# interfacing_board.net
KiCad netlist of a schematic drawn in EAGLE
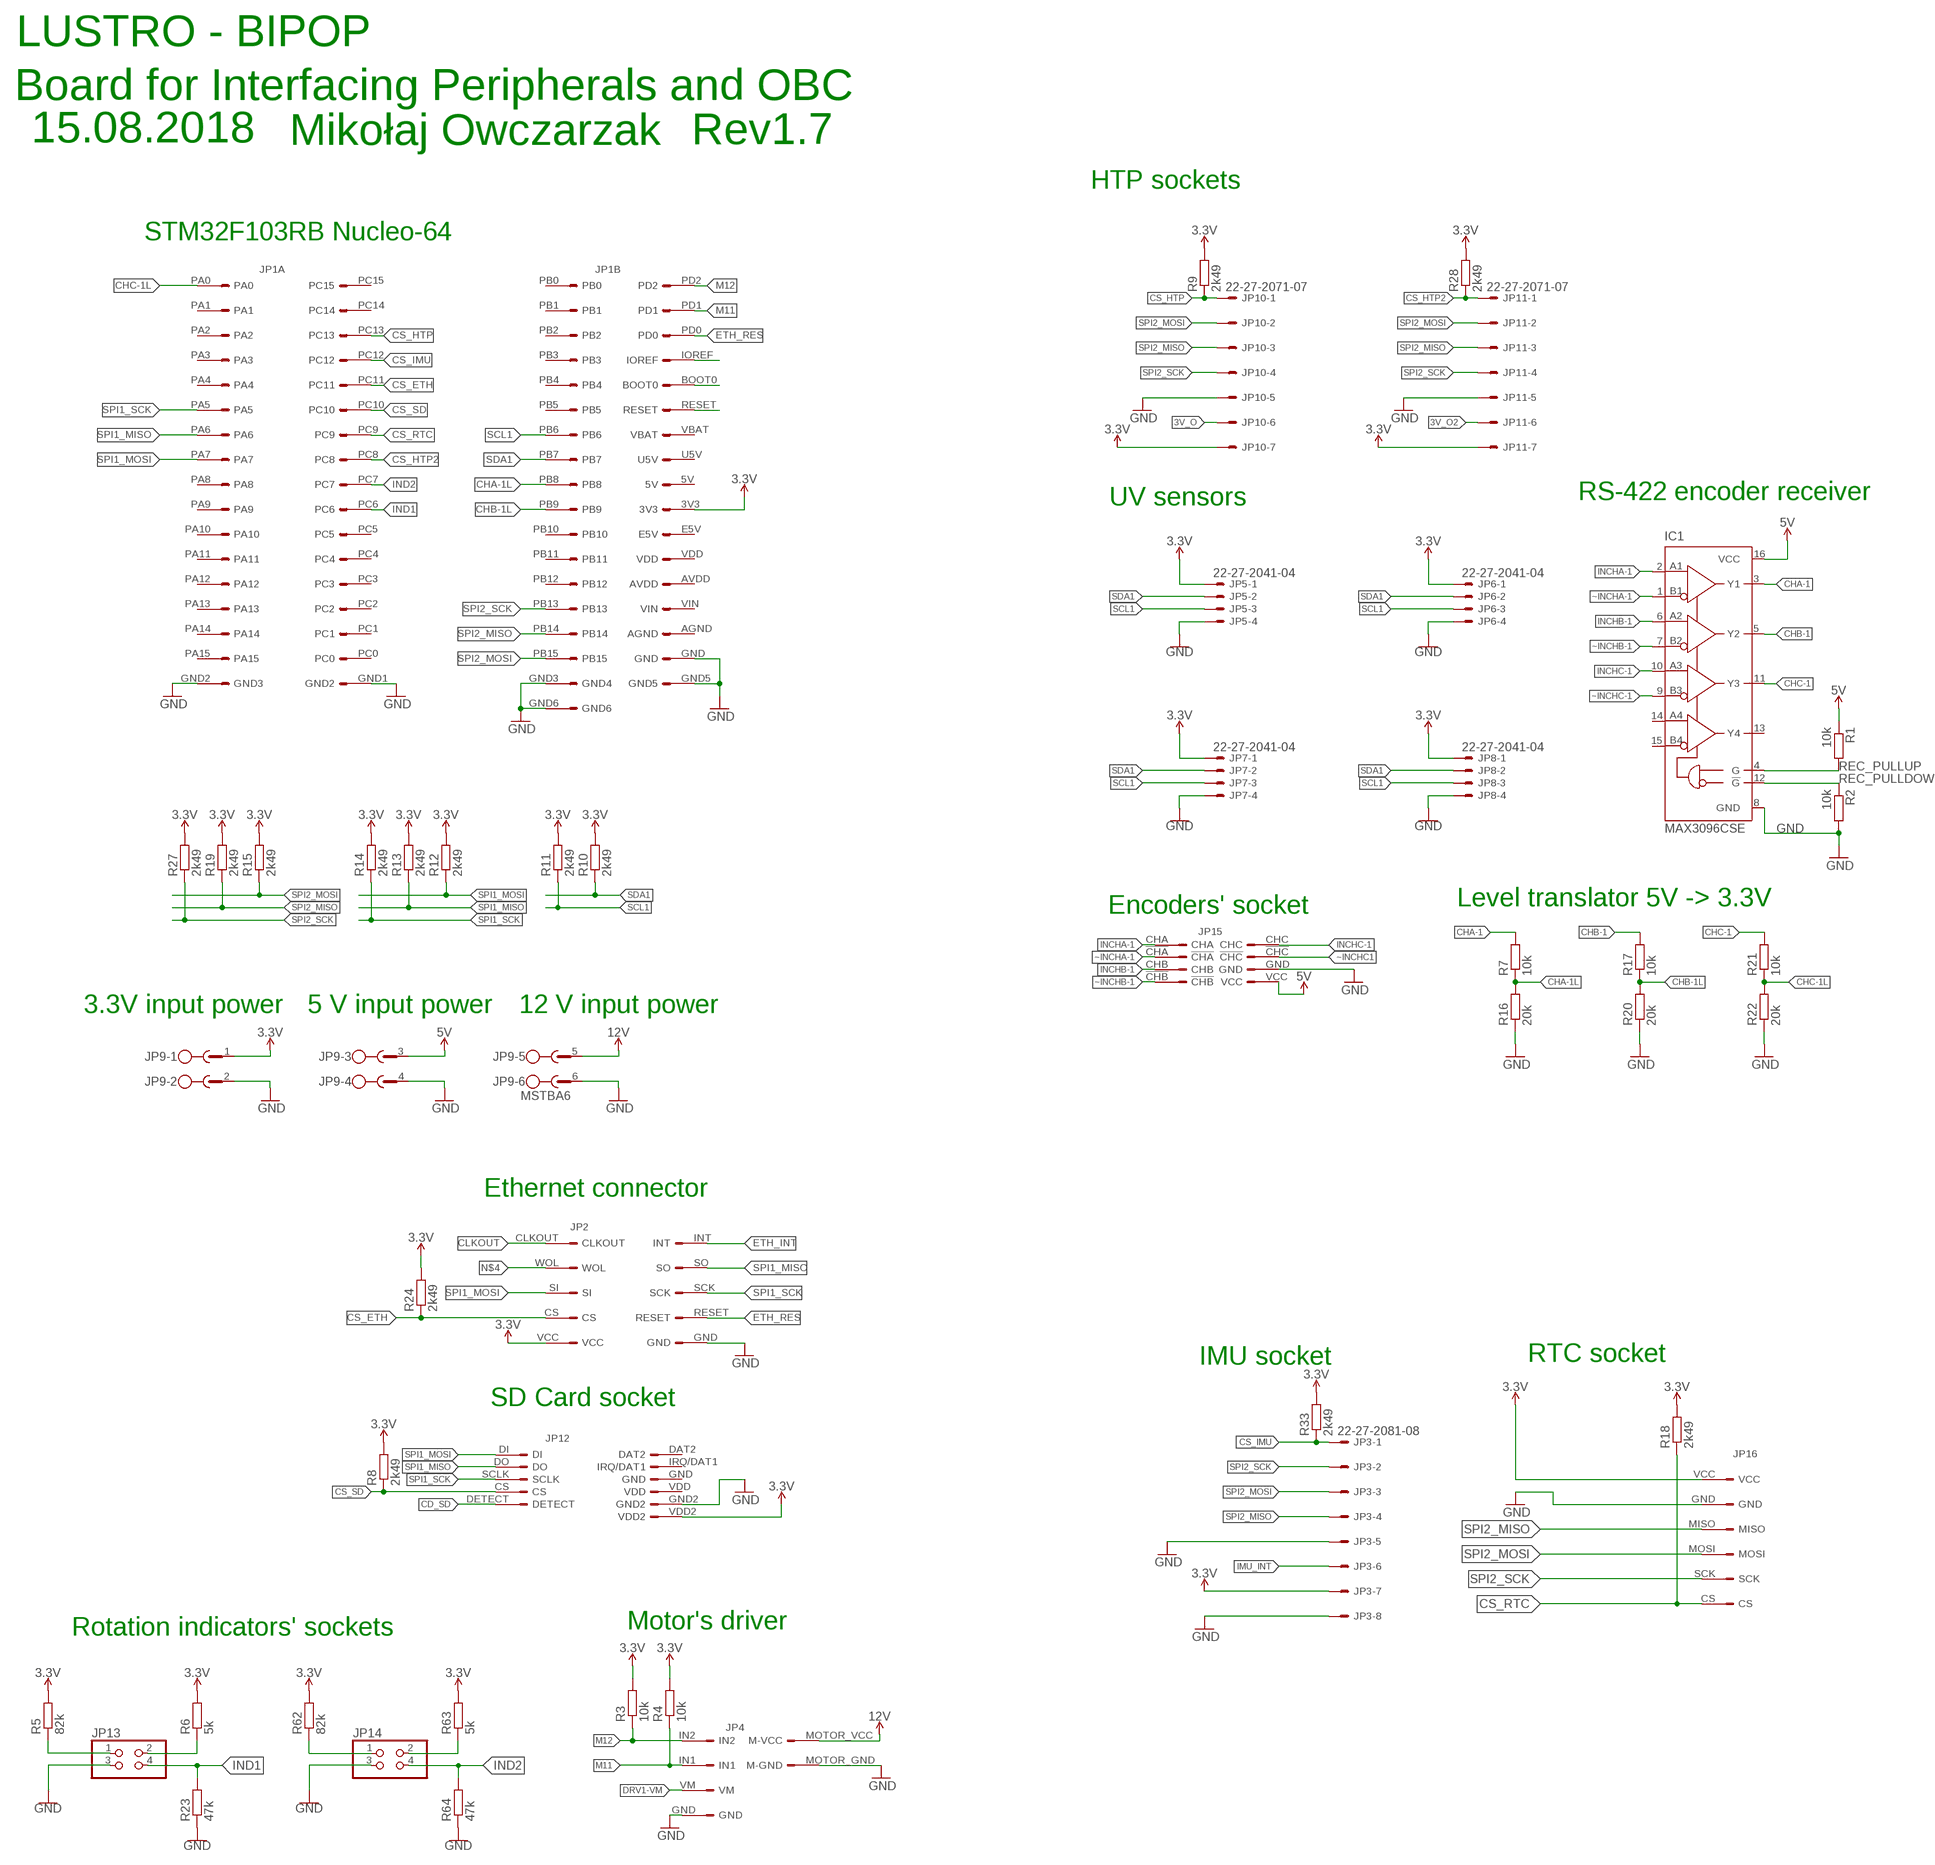
[diagram p0: schematic, sheet 1]

(export (version "E")
  (design (tool "Eeschema 10.0.6"))
  (components
    (comp (ref "IC1")
      (value "MAX3096CSE")
      (footprint "eagle-import:SO16")
      (fields (field (name "MF") "MAXIM") (field (name "MPN") "MAX3096CSE+"))
      (libsource (lib "eagle-import") (part "MAX309SE6C"))
    )
    (comp (ref "JP1A")
      (value "JP1B")
      (footprint "eagle-import:NUCLEO")
      (libsource (lib "eagle-import") (part "NUCLEOF103"))
    )
    (comp (ref "JP2")
      (value "ETHERNET")
      (footprint "eagle-import:ETHERNET")
      (libsource (lib "eagle-import") (part "ETHERNET"))
    )
    (comp (ref "JP3")
      (value "22-27-2081-08")
      (footprint "eagle-import:6410-08")
      (libsource (lib "eagle-import") (part "22-?-0827-2081"))
    )
    (comp (ref "JP4")
      (value "DRV8871")
      (footprint "eagle-import:DRIVER")
      (libsource (lib "eagle-import") (part "DRV8871"))
    )
    (comp (ref "JP5")
      (value "22-27-2041-04")
      (footprint "eagle-import:6410-04")
      (libsource (lib "eagle-import") (part "22-?-0427-2041"))
    )
    (comp (ref "JP6")
      (value "22-27-2041-04")
      (footprint "eagle-import:6410-04")
      (libsource (lib "eagle-import") (part "22-?-0427-2041"))
    )
    (comp (ref "JP7")
      (value "22-27-2041-04")
      (footprint "eagle-import:6410-04")
      (libsource (lib "eagle-import") (part "22-?-0427-2041"))
    )
    (comp (ref "JP8")
      (value "22-27-2041-04")
      (footprint "eagle-import:6410-04")
      (libsource (lib "eagle-import") (part "22-?-0427-2041"))
    )
    (comp (ref "JP9")
      (value "MSTBA6")
      (footprint "eagle-import:MSTBA6")
      (fields (field (name "MF") "FARNELL") (field (name "MPN") "1757284"))
      (libsource (lib "eagle-import") (part "MSTBA6"))
    )
    (comp (ref "JP10")
      (value "22-27-2071-07")
      (footprint "eagle-import:6410-07")
      (libsource (lib "eagle-import") (part "22-?-0727-2071"))
    )
    (comp (ref "JP11")
      (value "22-27-2071-07")
      (footprint "eagle-import:6410-07")
      (libsource (lib "eagle-import") (part "22-?-0727-2071"))
    )
    (comp (ref "JP12")
      (value "SD_2597")
      (footprint "eagle-import:SD")
      (libsource (lib "eagle-import") (part "SD_2597"))
    )
    (comp (ref "JP13")
      (value "PINHD-2X2")
      (footprint "eagle-import:2X02")
      (libsource (lib "eagle-import") (part "PINHD-2X2"))
    )
    (comp (ref "JP14")
      (value "PINHD-2X2")
      (footprint "eagle-import:2X02")
      (libsource (lib "eagle-import") (part "PINHD-2X2"))
    )
    (comp (ref "JP15")
      (value "ENX10")
      (footprint "eagle-import:SIL25")
      (libsource (lib "eagle-import") (part "ENX10"))
    )
    (comp (ref "JP16")
      (value "RTC_WAVESHARE")
      (footprint "eagle-import:RTC")
      (libsource (lib "eagle-import") (part "RTC_WAVESHARE"))
    )
    (comp (ref "R1")
      (value "10k")
      (footprint "eagle-import:M0805")
      (libsource (lib "eagle-import") (part "R-EU_M0805"))
    )
    (comp (ref "R2")
      (value "10k")
      (footprint "eagle-import:M0805")
      (libsource (lib "eagle-import") (part "R-EU_M0805"))
    )
    (comp (ref "R3")
      (value "10k")
      (footprint "eagle-import:M0805")
      (libsource (lib "eagle-import") (part "R-EU_M0805"))
    )
    (comp (ref "R4")
      (value "10k")
      (footprint "eagle-import:M0805")
      (libsource (lib "eagle-import") (part "R-EU_M0805"))
    )
    (comp (ref "R5")
      (value "82k")
      (footprint "eagle-import:M0805")
      (libsource (lib "eagle-import") (part "resistor_348_R-EU_M0805"))
    )
    (comp (ref "R6")
      (value "5k")
      (footprint "eagle-import:M0805")
      (libsource (lib "eagle-import") (part "resistor_348_R-EU_M0805"))
    )
    (comp (ref "R7")
      (value "10k")
      (footprint "eagle-import:M0805")
      (libsource (lib "eagle-import") (part "R-EU_M0805"))
    )
    (comp (ref "R8")
      (value "2k49")
      (footprint "eagle-import:M0805")
      (libsource (lib "eagle-import") (part "resistor_348_R-EU_M0805"))
    )
    (comp (ref "R9")
      (value "2k49")
      (footprint "eagle-import:M0805")
      (libsource (lib "eagle-import") (part "R-EU_M0805"))
    )
    (comp (ref "R10")
      (value "2k49")
      (footprint "eagle-import:M0805")
      (libsource (lib "eagle-import") (part "R-EU_M0805"))
    )
    (comp (ref "R11")
      (value "2k49")
      (footprint "eagle-import:M0805")
      (libsource (lib "eagle-import") (part "R-EU_M0805"))
    )
    (comp (ref "R12")
      (value "2k49")
      (footprint "eagle-import:M0805")
      (libsource (lib "eagle-import") (part "R-EU_M0805"))
    )
    (comp (ref "R13")
      (value "2k49")
      (footprint "eagle-import:M0805")
      (libsource (lib "eagle-import") (part "R-EU_M0805"))
    )
    (comp (ref "R14")
      (value "2k49")
      (footprint "eagle-import:M0805")
      (libsource (lib "eagle-import") (part "R-EU_M0805"))
    )
    (comp (ref "R15")
      (value "2k49")
      (footprint "eagle-import:M0805")
      (libsource (lib "eagle-import") (part "R-EU_M0805"))
    )
    (comp (ref "R16")
      (value "20k")
      (footprint "eagle-import:M0805")
      (libsource (lib "eagle-import") (part "R-EU_M0805"))
    )
    (comp (ref "R17")
      (value "10k")
      (footprint "eagle-import:M0805")
      (libsource (lib "eagle-import") (part "R-EU_M0805"))
    )
    (comp (ref "R18")
      (value "2k49")
      (footprint "eagle-import:R0805")
      (libsource (lib "eagle-import") (part "R-EU_R0805"))
    )
    (comp (ref "R19")
      (value "2k49")
      (footprint "eagle-import:M0805")
      (libsource (lib "eagle-import") (part "R-EU_M0805"))
    )
    (comp (ref "R20")
      (value "20k")
      (footprint "eagle-import:M0805")
      (libsource (lib "eagle-import") (part "R-EU_M0805"))
    )
    (comp (ref "R21")
      (value "10k")
      (footprint "eagle-import:M0805")
      (libsource (lib "eagle-import") (part "R-EU_M0805"))
    )
    (comp (ref "R22")
      (value "20k")
      (footprint "eagle-import:M0805")
      (libsource (lib "eagle-import") (part "R-EU_M0805"))
    )
    (comp (ref "R23")
      (value "47k")
      (footprint "eagle-import:M0805")
      (libsource (lib "eagle-import") (part "resistor_348_R-EU_M0805"))
    )
    (comp (ref "R24")
      (value "2k49")
      (footprint "eagle-import:M0805")
      (libsource (lib "eagle-import") (part "resistor_348_R-EU_M0805"))
    )
    (comp (ref "R27")
      (value "2k49")
      (footprint "eagle-import:M0805")
      (libsource (lib "eagle-import") (part "R-EU_M0805"))
    )
    (comp (ref "R28")
      (value "2k49")
      (footprint "eagle-import:M0805")
      (libsource (lib "eagle-import") (part "R-EU_M0805"))
    )
    (comp (ref "R33")
      (value "2k49")
      (footprint "eagle-import:M0805")
      (libsource (lib "eagle-import") (part "R-EU_M0805"))
    )
    (comp (ref "R62")
      (value "82k")
      (footprint "eagle-import:M0805")
      (libsource (lib "eagle-import") (part "resistor_348_R-EU_M0805"))
    )
    (comp (ref "R63")
      (value "5k")
      (footprint "eagle-import:M0805")
      (libsource (lib "eagle-import") (part "resistor_348_R-EU_M0805"))
    )
    (comp (ref "R64")
      (value "47k")
      (footprint "eagle-import:M0805")
      (libsource (lib "eagle-import") (part "resistor_348_R-EU_M0805"))
    )
  )
  (nets
    (net (code "1") (name "/REC_PULLDOWN") (class "Default")
      (node (ref "IC1") (pin "12") (pinfunction "~{G}_12") (pintype "input"))
      (node (ref "R2") (pin "1") (pinfunction "1_1") (pintype "passive"))
    )
    (net (code "2") (name "/REC_PULLUP") (class "Default")
      (node (ref "IC1") (pin "4") (pinfunction "G_4") (pintype "input"))
      (node (ref "R1") (pin "2") (pinfunction "2_2") (pintype "passive"))
    )
    (net (code "3") (name "/~{INCHA-1}") (class "Default")
      (node (ref "IC1") (pin "1") (pinfunction "B1_1") (pintype "output"))
      (node (ref "JP15") (pin "!CHA") (pinfunction "~{CHA}_!CHA") (pintype "bidirectional"))
    )
    (net (code "4") (name "/~{INCHB-1}") (class "Default")
      (node (ref "IC1") (pin "7") (pinfunction "B2_7") (pintype "output"))
      (node (ref "JP15") (pin "!CHB") (pinfunction "~{CHB}_!CHB") (pintype "bidirectional"))
    )
    (net (code "5") (name "/~{INCHC-1}") (class "Default")
      (node (ref "IC1") (pin "9") (pinfunction "B3_9") (pintype "output"))
    )
    (net (code "6") (name "/~{INCHC1}") (class "Default")
      (node (ref "JP15") (pin "!CHC") (pinfunction "~{CHC}_!CHC") (pintype "bidirectional"))
    )
    (net (code "7") (name "3.3V") (class "Default")
      (node (ref "JP10") (pin "7") (pinfunction "S_7") (pintype "passive"))
      (node (ref "JP11") (pin "7") (pinfunction "S_7") (pintype "passive"))
      (node (ref "JP12") (pin "VDD2") (pinfunction "VDD2_VDD2") (pintype "bidirectional"))
      (node (ref "JP16") (pin "VCC") (pinfunction "VCC_VCC") (pintype "bidirectional"))
      (node (ref "JP1A") (pin "3V3") (pinfunction "3V3_3V3") (pintype "bidirectional"))
      (node (ref "JP2") (pin "VCC") (pinfunction "VCC_VCC") (pintype "bidirectional"))
      (node (ref "JP3") (pin "7") (pinfunction "S_7") (pintype "passive"))
      (node (ref "JP5") (pin "1") (pinfunction "S_1") (pintype "passive"))
      (node (ref "JP6") (pin "1") (pinfunction "S_1") (pintype "passive"))
      (node (ref "JP7") (pin "1") (pinfunction "S_1") (pintype "passive"))
      (node (ref "JP8") (pin "1") (pinfunction "S_1") (pintype "passive"))
      (node (ref "JP9") (pin "1") (pinfunction "1_1") (pintype "passive"))
      (node (ref "R10") (pin "2") (pinfunction "2_2") (pintype "passive"))
      (node (ref "R11") (pin "2") (pinfunction "2_2") (pintype "passive"))
      (node (ref "R12") (pin "2") (pinfunction "2_2") (pintype "passive"))
      (node (ref "R13") (pin "2") (pinfunction "2_2") (pintype "passive"))
      (node (ref "R14") (pin "2") (pinfunction "2_2") (pintype "passive"))
      (node (ref "R15") (pin "2") (pinfunction "2_2") (pintype "passive"))
      (node (ref "R18") (pin "2") (pinfunction "2_2") (pintype "passive"))
      (node (ref "R19") (pin "2") (pinfunction "2_2") (pintype "passive"))
      (node (ref "R24") (pin "2") (pinfunction "2_2") (pintype "passive"))
      (node (ref "R27") (pin "2") (pinfunction "2_2") (pintype "passive"))
      (node (ref "R28") (pin "2") (pinfunction "2_2") (pintype "passive"))
      (node (ref "R3") (pin "2") (pinfunction "2_2") (pintype "passive"))
      (node (ref "R33") (pin "2") (pinfunction "2_2") (pintype "passive"))
      (node (ref "R4") (pin "2") (pinfunction "2_2") (pintype "passive"))
      (node (ref "R5") (pin "2") (pinfunction "2_2") (pintype "passive"))
      (node (ref "R6") (pin "2") (pinfunction "2_2") (pintype "passive"))
      (node (ref "R62") (pin "2") (pinfunction "2_2") (pintype "passive"))
      (node (ref "R63") (pin "2") (pinfunction "2_2") (pintype "passive"))
      (node (ref "R8") (pin "2") (pinfunction "2_2") (pintype "passive"))
      (node (ref "R9") (pin "2") (pinfunction "2_2") (pintype "passive"))
    )
    (net (code "8") (name "3V_O") (class "Default")
      (node (ref "JP10") (pin "6") (pinfunction "S_6") (pintype "passive"))
    )
    (net (code "9") (name "3V_O2") (class "Default")
      (node (ref "JP11") (pin "6") (pinfunction "S_6") (pintype "passive"))
    )
    (net (code "10") (name "5V") (class "Default")
      (node (ref "IC1") (pin "16") (pinfunction "VCC_16") (pintype "output"))
      (node (ref "JP15") (pin "VCC") (pinfunction "VCC_VCC") (pintype "bidirectional"))
      (node (ref "JP9") (pin "3") (pinfunction "1_3") (pintype "passive"))
      (node (ref "R1") (pin "1") (pinfunction "1_1") (pintype "passive"))
    )
    (net (code "11") (name "12V") (class "Default")
      (node (ref "JP4") (pin "MOTOR_VCC") (pinfunction "M-VCC_MOTOR_VCC") (pintype "bidirectional"))
      (node (ref "JP9") (pin "5") (pinfunction "1_5") (pintype "passive"))
    )
    (net (code "12") (name "CD_SD") (class "Default")
      (node (ref "JP12") (pin "DETECT") (pinfunction "DETECT_DETECT") (pintype "bidirectional"))
    )
    (net (code "13") (name "CHA-1") (class "Default")
      (node (ref "IC1") (pin "3") (pinfunction "Y1_3") (pintype "output"))
      (node (ref "R7") (pin "2") (pinfunction "2_2") (pintype "passive"))
    )
    (net (code "14") (name "CHA-1L") (class "Default")
      (node (ref "JP1A") (pin "PB8") (pinfunction "PB8_PB8") (pintype "bidirectional"))
      (node (ref "R16") (pin "2") (pinfunction "2_2") (pintype "passive"))
      (node (ref "R7") (pin "1") (pinfunction "1_1") (pintype "passive"))
    )
    (net (code "15") (name "CHB-1") (class "Default")
      (node (ref "IC1") (pin "5") (pinfunction "Y2_5") (pintype "output"))
      (node (ref "R17") (pin "2") (pinfunction "2_2") (pintype "passive"))
    )
    (net (code "16") (name "CHB-1L") (class "Default")
      (node (ref "JP1A") (pin "PB9") (pinfunction "PB9_PB9") (pintype "bidirectional"))
      (node (ref "R17") (pin "1") (pinfunction "1_1") (pintype "passive"))
      (node (ref "R20") (pin "2") (pinfunction "2_2") (pintype "passive"))
    )
    (net (code "17") (name "CHC-1") (class "Default")
      (node (ref "IC1") (pin "11") (pinfunction "Y3_11") (pintype "output"))
      (node (ref "R21") (pin "2") (pinfunction "2_2") (pintype "passive"))
    )
    (net (code "18") (name "CHC-1L") (class "Default")
      (node (ref "JP1A") (pin "PA0") (pinfunction "PA0_PA0") (pintype "bidirectional"))
      (node (ref "R21") (pin "1") (pinfunction "1_1") (pintype "passive"))
      (node (ref "R22") (pin "2") (pinfunction "2_2") (pintype "passive"))
    )
    (net (code "19") (name "CLKOUT") (class "Default")
      (node (ref "JP2") (pin "CLKOUT") (pinfunction "CLKOUT_CLKOUT") (pintype "bidirectional"))
    )
    (net (code "20") (name "CS_ETH") (class "Default")
      (node (ref "JP1A") (pin "PC11") (pinfunction "PC11_PC11") (pintype "bidirectional"))
      (node (ref "JP2") (pin "CS") (pinfunction "CS_CS") (pintype "bidirectional"))
      (node (ref "R24") (pin "1") (pinfunction "1_1") (pintype "passive"))
    )
    (net (code "21") (name "CS_HTP") (class "Default")
      (node (ref "JP10") (pin "1") (pinfunction "S_1") (pintype "passive"))
      (node (ref "JP1A") (pin "PC13") (pinfunction "PC13_PC13") (pintype "bidirectional"))
      (node (ref "R9") (pin "1") (pinfunction "1_1") (pintype "passive"))
    )
    (net (code "22") (name "CS_HTP2") (class "Default")
      (node (ref "JP11") (pin "1") (pinfunction "S_1") (pintype "passive"))
      (node (ref "JP1A") (pin "PC8") (pinfunction "PC8_PC8") (pintype "bidirectional"))
      (node (ref "R28") (pin "1") (pinfunction "1_1") (pintype "passive"))
    )
    (net (code "23") (name "CS_IMU") (class "Default")
      (node (ref "JP1A") (pin "PC12") (pinfunction "PC12_PC12") (pintype "bidirectional"))
      (node (ref "JP3") (pin "1") (pinfunction "S_1") (pintype "passive"))
      (node (ref "R33") (pin "1") (pinfunction "1_1") (pintype "passive"))
    )
    (net (code "24") (name "CS_RTC") (class "Default")
      (node (ref "JP16") (pin "CS") (pinfunction "CS_CS") (pintype "bidirectional"))
      (node (ref "JP1A") (pin "PC9") (pinfunction "PC9_PC9") (pintype "bidirectional"))
      (node (ref "R18") (pin "1") (pinfunction "1_1") (pintype "passive"))
    )
    (net (code "25") (name "CS_SD") (class "Default")
      (node (ref "JP12") (pin "CS") (pinfunction "CS_CS") (pintype "bidirectional"))
      (node (ref "JP1A") (pin "PC10") (pinfunction "PC10_PC10") (pintype "bidirectional"))
      (node (ref "R8") (pin "1") (pinfunction "1_1") (pintype "passive"))
    )
    (net (code "26") (name "DRV1-VM") (class "Default")
      (node (ref "JP4") (pin "VM") (pinfunction "VM_VM") (pintype "bidirectional"))
    )
    (net (code "27") (name "ETH_INT") (class "Default")
      (node (ref "JP2") (pin "INT") (pinfunction "INT_INT") (pintype "bidirectional"))
    )
    (net (code "28") (name "ETH_RES") (class "Default")
      (node (ref "JP1A") (pin "PD0") (pinfunction "PD0_PD0") (pintype "bidirectional"))
      (node (ref "JP2") (pin "RESET") (pinfunction "RESET_RESET") (pintype "bidirectional"))
    )
    (net (code "29") (name "GND") (class "Default")
      (node (ref "IC1") (pin "8") (pinfunction "GND_8") (pintype "power_in"))
      (node (ref "JP10") (pin "5") (pinfunction "S_5") (pintype "passive"))
      (node (ref "JP11") (pin "5") (pinfunction "S_5") (pintype "passive"))
      (node (ref "JP12") (pin "GND2") (pinfunction "GND2_GND2") (pintype "bidirectional"))
      (node (ref "JP13") (pin "3") (pinfunction "3_3") (pintype "passive"))
      (node (ref "JP14") (pin "3") (pinfunction "3_3") (pintype "passive"))
      (node (ref "JP15") (pin "GND") (pinfunction "GND_GND") (pintype "bidirectional"))
      (node (ref "JP16") (pin "GND") (pinfunction "GND_GND") (pintype "bidirectional"))
      (node (ref "JP1A") (pin "GND") (pinfunction "GND_GND") (pintype "bidirectional"))
      (node (ref "JP1A") (pin "GND1") (pinfunction "GND2_GND1") (pintype "bidirectional"))
      (node (ref "JP1A") (pin "GND2") (pinfunction "GND3_GND2") (pintype "bidirectional"))
      (node (ref "JP1A") (pin "GND3") (pinfunction "GND4_GND3") (pintype "bidirectional"))
      (node (ref "JP1A") (pin "GND5") (pinfunction "GND5_GND5") (pintype "bidirectional"))
      (node (ref "JP1A") (pin "GND6") (pinfunction "GND6_GND6") (pintype "bidirectional"))
      (node (ref "JP2") (pin "GND") (pinfunction "GND_GND") (pintype "bidirectional"))
      (node (ref "JP3") (pin "5") (pinfunction "S_5") (pintype "passive"))
      (node (ref "JP3") (pin "8") (pinfunction "S_8") (pintype "passive"))
      (node (ref "JP4") (pin "GND") (pinfunction "GND_GND") (pintype "bidirectional"))
      (node (ref "JP4") (pin "MOTOR_GND") (pinfunction "M-GND_MOTOR_GND") (pintype "bidirectional"))
      (node (ref "JP5") (pin "4") (pinfunction "S_4") (pintype "passive"))
      (node (ref "JP6") (pin "4") (pinfunction "S_4") (pintype "passive"))
      (node (ref "JP7") (pin "4") (pinfunction "S_4") (pintype "passive"))
      (node (ref "JP8") (pin "4") (pinfunction "S_4") (pintype "passive"))
      (node (ref "JP9") (pin "2") (pinfunction "1_2") (pintype "passive"))
      (node (ref "JP9") (pin "4") (pinfunction "1_4") (pintype "passive"))
      (node (ref "JP9") (pin "6") (pinfunction "1_6") (pintype "passive"))
      (node (ref "R16") (pin "1") (pinfunction "1_1") (pintype "passive"))
      (node (ref "R2") (pin "2") (pinfunction "2_2") (pintype "passive"))
      (node (ref "R20") (pin "1") (pinfunction "1_1") (pintype "passive"))
      (node (ref "R22") (pin "1") (pinfunction "1_1") (pintype "passive"))
      (node (ref "R23") (pin "1") (pinfunction "1_1") (pintype "passive"))
      (node (ref "R64") (pin "1") (pinfunction "1_1") (pintype "passive"))
    )
    (net (code "30") (name "IMU_INT") (class "Default")
      (node (ref "JP3") (pin "6") (pinfunction "S_6") (pintype "passive"))
    )
    (net (code "31") (name "INCHA-1") (class "Default")
      (node (ref "IC1") (pin "2") (pinfunction "A1_2") (pintype "output"))
      (node (ref "JP15") (pin "CHA") (pinfunction "CHA_CHA") (pintype "bidirectional"))
    )
    (net (code "32") (name "INCHB-1") (class "Default")
      (node (ref "IC1") (pin "6") (pinfunction "A2_6") (pintype "output"))
      (node (ref "JP15") (pin "CHB") (pinfunction "CHB_CHB") (pintype "bidirectional"))
    )
    (net (code "33") (name "INCHC-1") (class "Default")
      (node (ref "IC1") (pin "10") (pinfunction "A3_10") (pintype "output"))
      (node (ref "JP15") (pin "CHC") (pinfunction "CHC_CHC") (pintype "bidirectional"))
    )
    (net (code "34") (name "IND1") (class "Default")
      (node (ref "JP13") (pin "4") (pinfunction "4_4") (pintype "passive"))
      (node (ref "JP1A") (pin "PC6") (pinfunction "PC6_PC6") (pintype "bidirectional"))
      (node (ref "R23") (pin "2") (pinfunction "2_2") (pintype "passive"))
    )
    (net (code "35") (name "IND2") (class "Default")
      (node (ref "JP14") (pin "4") (pinfunction "4_4") (pintype "passive"))
      (node (ref "JP1A") (pin "PC7") (pinfunction "PC7_PC7") (pintype "bidirectional"))
      (node (ref "R64") (pin "2") (pinfunction "2_2") (pintype "passive"))
    )
    (net (code "36") (name "M11") (class "Default")
      (node (ref "JP1A") (pin "PD1") (pinfunction "PD1_PD1") (pintype "bidirectional"))
      (node (ref "JP4") (pin "IN1") (pinfunction "IN1_IN1") (pintype "bidirectional"))
      (node (ref "R4") (pin "1") (pinfunction "1_1") (pintype "passive"))
    )
    (net (code "37") (name "M12") (class "Default")
      (node (ref "JP1A") (pin "PD2") (pinfunction "PD2_PD2") (pintype "bidirectional"))
      (node (ref "JP4") (pin "IN2") (pinfunction "IN2_IN2") (pintype "bidirectional"))
      (node (ref "R3") (pin "1") (pinfunction "1_1") (pintype "passive"))
    )
    (net (code "38") (name "N$4") (class "Default")
      (node (ref "JP2") (pin "WOL") (pinfunction "WOL_WOL") (pintype "bidirectional"))
    )
    (net (code "39") (name "Net-(JP13-Pad1)") (class "Default")
      (node (ref "JP13") (pin "1") (pinfunction "1_1") (pintype "passive"))
      (node (ref "R5") (pin "1") (pinfunction "1_1") (pintype "passive"))
    )
    (net (code "40") (name "Net-(JP13-Pad2)") (class "Default")
      (node (ref "JP13") (pin "2") (pinfunction "2_2") (pintype "passive"))
      (node (ref "R6") (pin "1") (pinfunction "1_1") (pintype "passive"))
    )
    (net (code "41") (name "Net-(JP14-Pad1)") (class "Default")
      (node (ref "JP14") (pin "1") (pinfunction "1_1") (pintype "passive"))
      (node (ref "R62") (pin "1") (pinfunction "1_1") (pintype "passive"))
    )
    (net (code "42") (name "Net-(JP14-Pad2)") (class "Default")
      (node (ref "JP14") (pin "2") (pinfunction "2_2") (pintype "passive"))
      (node (ref "R63") (pin "1") (pinfunction "1_1") (pintype "passive"))
    )
    (net (code "43") (name "SCL1") (class "Default")
      (node (ref "JP1A") (pin "PB6") (pinfunction "PB6_PB6") (pintype "bidirectional"))
      (node (ref "JP5") (pin "3") (pinfunction "S_3") (pintype "passive"))
      (node (ref "JP6") (pin "3") (pinfunction "S_3") (pintype "passive"))
      (node (ref "JP7") (pin "3") (pinfunction "S_3") (pintype "passive"))
      (node (ref "JP8") (pin "3") (pinfunction "S_3") (pintype "passive"))
      (node (ref "R11") (pin "1") (pinfunction "1_1") (pintype "passive"))
    )
    (net (code "44") (name "SDA1") (class "Default")
      (node (ref "JP1A") (pin "PB7") (pinfunction "PB7_PB7") (pintype "bidirectional"))
      (node (ref "JP5") (pin "2") (pinfunction "S_2") (pintype "passive"))
      (node (ref "JP6") (pin "2") (pinfunction "S_2") (pintype "passive"))
      (node (ref "JP7") (pin "2") (pinfunction "S_2") (pintype "passive"))
      (node (ref "JP8") (pin "2") (pinfunction "S_2") (pintype "passive"))
      (node (ref "R10") (pin "1") (pinfunction "1_1") (pintype "passive"))
    )
    (net (code "45") (name "SPI1_MISO") (class "Default")
      (node (ref "JP12") (pin "DO") (pinfunction "DO_DO") (pintype "bidirectional"))
      (node (ref "JP1A") (pin "PA6") (pinfunction "PA6_PA6") (pintype "bidirectional"))
      (node (ref "JP2") (pin "SO") (pinfunction "SO_SO") (pintype "bidirectional"))
      (node (ref "R13") (pin "1") (pinfunction "1_1") (pintype "passive"))
    )
    (net (code "46") (name "SPI1_MOSI") (class "Default")
      (node (ref "JP12") (pin "DI") (pinfunction "DI_DI") (pintype "bidirectional"))
      (node (ref "JP1A") (pin "PA7") (pinfunction "PA7_PA7") (pintype "bidirectional"))
      (node (ref "JP2") (pin "SI") (pinfunction "SI_SI") (pintype "bidirectional"))
      (node (ref "R12") (pin "1") (pinfunction "1_1") (pintype "passive"))
    )
    (net (code "47") (name "SPI1_SCK") (class "Default")
      (node (ref "JP12") (pin "SCLK") (pinfunction "SCLK_SCLK") (pintype "bidirectional"))
      (node (ref "JP1A") (pin "PA5") (pinfunction "PA5_PA5") (pintype "bidirectional"))
      (node (ref "JP2") (pin "SCK") (pinfunction "SCK_SCK") (pintype "bidirectional"))
      (node (ref "R14") (pin "1") (pinfunction "1_1") (pintype "passive"))
    )
    (net (code "48") (name "SPI2_MISO") (class "Default")
      (node (ref "JP10") (pin "3") (pinfunction "S_3") (pintype "passive"))
      (node (ref "JP11") (pin "3") (pinfunction "S_3") (pintype "passive"))
      (node (ref "JP16") (pin "MISO") (pinfunction "MISO_MISO") (pintype "bidirectional"))
      (node (ref "JP1A") (pin "PB14") (pinfunction "PB14_PB14") (pintype "bidirectional"))
      (node (ref "JP3") (pin "4") (pinfunction "S_4") (pintype "passive"))
      (node (ref "R19") (pin "1") (pinfunction "1_1") (pintype "passive"))
    )
    (net (code "49") (name "SPI2_MOSI") (class "Default")
      (node (ref "JP10") (pin "2") (pinfunction "S_2") (pintype "passive"))
      (node (ref "JP11") (pin "2") (pinfunction "S_2") (pintype "passive"))
      (node (ref "JP16") (pin "MOSI") (pinfunction "MOSI_MOSI") (pintype "bidirectional"))
      (node (ref "JP1A") (pin "PB15") (pinfunction "PB15_PB15") (pintype "bidirectional"))
      (node (ref "JP3") (pin "3") (pinfunction "S_3") (pintype "passive"))
      (node (ref "R15") (pin "1") (pinfunction "1_1") (pintype "passive"))
    )
    (net (code "50") (name "SPI2_SCK") (class "Default")
      (node (ref "JP10") (pin "4") (pinfunction "S_4") (pintype "passive"))
      (node (ref "JP11") (pin "4") (pinfunction "S_4") (pintype "passive"))
      (node (ref "JP16") (pin "SCK") (pinfunction "SCK_SCK") (pintype "bidirectional"))
      (node (ref "JP1A") (pin "PB13") (pinfunction "PB13_PB13") (pintype "bidirectional"))
      (node (ref "JP3") (pin "2") (pinfunction "S_2") (pintype "passive"))
      (node (ref "R27") (pin "1") (pinfunction "1_1") (pintype "passive"))
    )
    (net (code "51") (name "unconnected-(IC1-A4-Pad14)") (class "Default")
      (node (ref "IC1") (pin "14") (pinfunction "A4_14") (pintype "output"))
    )
    (net (code "52") (name "unconnected-(IC1-B4-Pad15)") (class "Default")
      (node (ref "IC1") (pin "15") (pinfunction "B4_15") (pintype "output"))
    )
    (net (code "53") (name "unconnected-(IC1-Y4-Pad13)") (class "Default")
      (node (ref "IC1") (pin "13") (pinfunction "Y4_13") (pintype "output"))
    )
    (net (code "54") (name "unconnected-(JP1A-Pad5V)") (class "Default")
      (node (ref "JP1A") (pin "5V") (pinfunction "5V_5V") (pintype "bidirectional"))
    )
    (net (code "55") (name "unconnected-(JP1A-PadAGND)") (class "Default")
      (node (ref "JP1A") (pin "AGND") (pinfunction "AGND_AGND") (pintype "bidirectional"))
    )
    (net (code "56") (name "unconnected-(JP1A-PadAVDD)") (class "Default")
      (node (ref "JP1A") (pin "AVDD") (pinfunction "AVDD_AVDD") (pintype "bidirectional"))
    )
    (net (code "57") (name "unconnected-(JP1A-PadBOOT0)") (class "Default")
      (node (ref "JP1A") (pin "BOOT0") (pinfunction "BOOT0_BOOT0") (pintype "bidirectional"))
    )
    (net (code "58") (name "unconnected-(JP1A-PadE5V)") (class "Default")
      (node (ref "JP1A") (pin "E5V") (pinfunction "E5V_E5V") (pintype "bidirectional"))
    )
    (net (code "59") (name "unconnected-(JP1A-PadIOREF)") (class "Default")
      (node (ref "JP1A") (pin "IOREF") (pinfunction "IOREF_IOREF") (pintype "bidirectional"))
    )
    (net (code "60") (name "unconnected-(JP1A-PadPA1)") (class "Default")
      (node (ref "JP1A") (pin "PA1") (pinfunction "PA1_PA1") (pintype "bidirectional"))
    )
    (net (code "61") (name "unconnected-(JP1A-PadPA2)") (class "Default")
      (node (ref "JP1A") (pin "PA2") (pinfunction "PA2_PA2") (pintype "bidirectional"))
    )
    (net (code "62") (name "unconnected-(JP1A-PadPA3)") (class "Default")
      (node (ref "JP1A") (pin "PA3") (pinfunction "PA3_PA3") (pintype "bidirectional"))
    )
    (net (code "63") (name "unconnected-(JP1A-PadPA4)") (class "Default")
      (node (ref "JP1A") (pin "PA4") (pinfunction "PA4_PA4") (pintype "bidirectional"))
    )
    (net (code "64") (name "unconnected-(JP1A-PadPA8)") (class "Default")
      (node (ref "JP1A") (pin "PA8") (pinfunction "PA8_PA8") (pintype "bidirectional"))
    )
    (net (code "65") (name "unconnected-(JP1A-PadPA9)") (class "Default")
      (node (ref "JP1A") (pin "PA9") (pinfunction "PA9_PA9") (pintype "bidirectional"))
    )
    (net (code "66") (name "unconnected-(JP1A-PadPA10)") (class "Default")
      (node (ref "JP1A") (pin "PA10") (pinfunction "PA10_PA10") (pintype "bidirectional"))
    )
    (net (code "67") (name "unconnected-(JP1A-PadPA11)") (class "Default")
      (node (ref "JP1A") (pin "PA11") (pinfunction "PA11_PA11") (pintype "bidirectional"))
    )
    (net (code "68") (name "unconnected-(JP1A-PadPA12)") (class "Default")
      (node (ref "JP1A") (pin "PA12") (pinfunction "PA12_PA12") (pintype "bidirectional"))
    )
    (net (code "69") (name "unconnected-(JP1A-PadPA13)") (class "Default")
      (node (ref "JP1A") (pin "PA13") (pinfunction "PA13_PA13") (pintype "bidirectional"))
    )
    (net (code "70") (name "unconnected-(JP1A-PadPA14)") (class "Default")
      (node (ref "JP1A") (pin "PA14") (pinfunction "PA14_PA14") (pintype "bidirectional"))
    )
    (net (code "71") (name "unconnected-(JP1A-PadPA15)") (class "Default")
      (node (ref "JP1A") (pin "PA15") (pinfunction "PA15_PA15") (pintype "bidirectional"))
    )
    (net (code "72") (name "unconnected-(JP1A-PadPB0)") (class "Default")
      (node (ref "JP1A") (pin "PB0") (pinfunction "PB0_PB0") (pintype "bidirectional"))
    )
    (net (code "73") (name "unconnected-(JP1A-PadPB1)") (class "Default")
      (node (ref "JP1A") (pin "PB1") (pinfunction "PB1_PB1") (pintype "bidirectional"))
    )
    (net (code "74") (name "unconnected-(JP1A-PadPB2)") (class "Default")
      (node (ref "JP1A") (pin "PB2") (pinfunction "PB2_PB2") (pintype "bidirectional"))
    )
    (net (code "75") (name "unconnected-(JP1A-PadPB3)") (class "Default")
      (node (ref "JP1A") (pin "PB3") (pinfunction "PB3_PB3") (pintype "bidirectional"))
    )
    (net (code "76") (name "unconnected-(JP1A-PadPB4)") (class "Default")
      (node (ref "JP1A") (pin "PB4") (pinfunction "PB4_PB4") (pintype "bidirectional"))
    )
    (net (code "77") (name "unconnected-(JP1A-PadPB5)") (class "Default")
      (node (ref "JP1A") (pin "PB5") (pinfunction "PB5_PB5") (pintype "bidirectional"))
    )
    (net (code "78") (name "unconnected-(JP1A-PadPB10)") (class "Default")
      (node (ref "JP1A") (pin "PB10") (pinfunction "PB10_PB10") (pintype "bidirectional"))
    )
    (net (code "79") (name "unconnected-(JP1A-PadPB11)") (class "Default")
      (node (ref "JP1A") (pin "PB11") (pinfunction "PB11_PB11") (pintype "bidirectional"))
    )
    (net (code "80") (name "unconnected-(JP1A-PadPB12)") (class "Default")
      (node (ref "JP1A") (pin "PB12") (pinfunction "PB12_PB12") (pintype "bidirectional"))
    )
    (net (code "81") (name "unconnected-(JP1A-PadPC0)") (class "Default")
      (node (ref "JP1A") (pin "PC0") (pinfunction "PC0_PC0") (pintype "bidirectional"))
    )
    (net (code "82") (name "unconnected-(JP1A-PadPC1)") (class "Default")
      (node (ref "JP1A") (pin "PC1") (pinfunction "PC1_PC1") (pintype "bidirectional"))
    )
    (net (code "83") (name "unconnected-(JP1A-PadPC2)") (class "Default")
      (node (ref "JP1A") (pin "PC2") (pinfunction "PC2_PC2") (pintype "bidirectional"))
    )
    (net (code "84") (name "unconnected-(JP1A-PadPC3)") (class "Default")
      (node (ref "JP1A") (pin "PC3") (pinfunction "PC3_PC3") (pintype "bidirectional"))
    )
    (net (code "85") (name "unconnected-(JP1A-PadPC4)") (class "Default")
      (node (ref "JP1A") (pin "PC4") (pinfunction "PC4_PC4") (pintype "bidirectional"))
    )
    (net (code "86") (name "unconnected-(JP1A-PadPC5)") (class "Default")
      (node (ref "JP1A") (pin "PC5") (pinfunction "PC5_PC5") (pintype "bidirectional"))
    )
    (net (code "87") (name "unconnected-(JP1A-PadPC14)") (class "Default")
      (node (ref "JP1A") (pin "PC14") (pinfunction "PC14_PC14") (pintype "bidirectional"))
    )
    (net (code "88") (name "unconnected-(JP1A-PadPC15)") (class "Default")
      (node (ref "JP1A") (pin "PC15") (pinfunction "PC15_PC15") (pintype "bidirectional"))
    )
    (net (code "89") (name "unconnected-(JP1A-PadRESET)") (class "Default")
      (node (ref "JP1A") (pin "RESET") (pinfunction "RESET_RESET") (pintype "bidirectional"))
    )
    (net (code "90") (name "unconnected-(JP1A-PadU5V)") (class "Default")
      (node (ref "JP1A") (pin "U5V") (pinfunction "U5V_U5V") (pintype "bidirectional"))
    )
    (net (code "91") (name "unconnected-(JP1A-PadVBAT)") (class "Default")
      (node (ref "JP1A") (pin "VBAT") (pinfunction "VBAT_VBAT") (pintype "bidirectional"))
    )
    (net (code "92") (name "unconnected-(JP1A-PadVDD)") (class "Default")
      (node (ref "JP1A") (pin "VDD") (pinfunction "VDD_VDD") (pintype "bidirectional"))
    )
    (net (code "93") (name "unconnected-(JP1A-PadVIN)") (class "Default")
      (node (ref "JP1A") (pin "VIN") (pinfunction "VIN_VIN") (pintype "bidirectional"))
    )
    (net (code "94") (name "unconnected-(JP12-PadDAT2)") (class "Default")
      (node (ref "JP12") (pin "DAT2") (pinfunction "DAT2_DAT2") (pintype "bidirectional"))
    )
    (net (code "95") (name "unconnected-(JP12-PadGND)") (class "Default")
      (node (ref "JP12") (pin "GND") (pinfunction "GND_GND") (pintype "bidirectional"))
    )
    (net (code "96") (name "unconnected-(JP12-PadIRQ{slash}DAT1)") (class "Default")
      (node (ref "JP12") (pin "IRQ/DAT1") (pinfunction "IRQ/DAT1_IRQ/DAT1") (pintype "bidirectional"))
    )
    (net (code "97") (name "unconnected-(JP12-PadVDD)") (class "Default")
      (node (ref "JP12") (pin "VDD") (pinfunction "VDD_VDD") (pintype "bidirectional"))
    )
  )
)
